# SysP_Uebersicht.net
KiCad netlist of a schematic drawn in Altium Designer
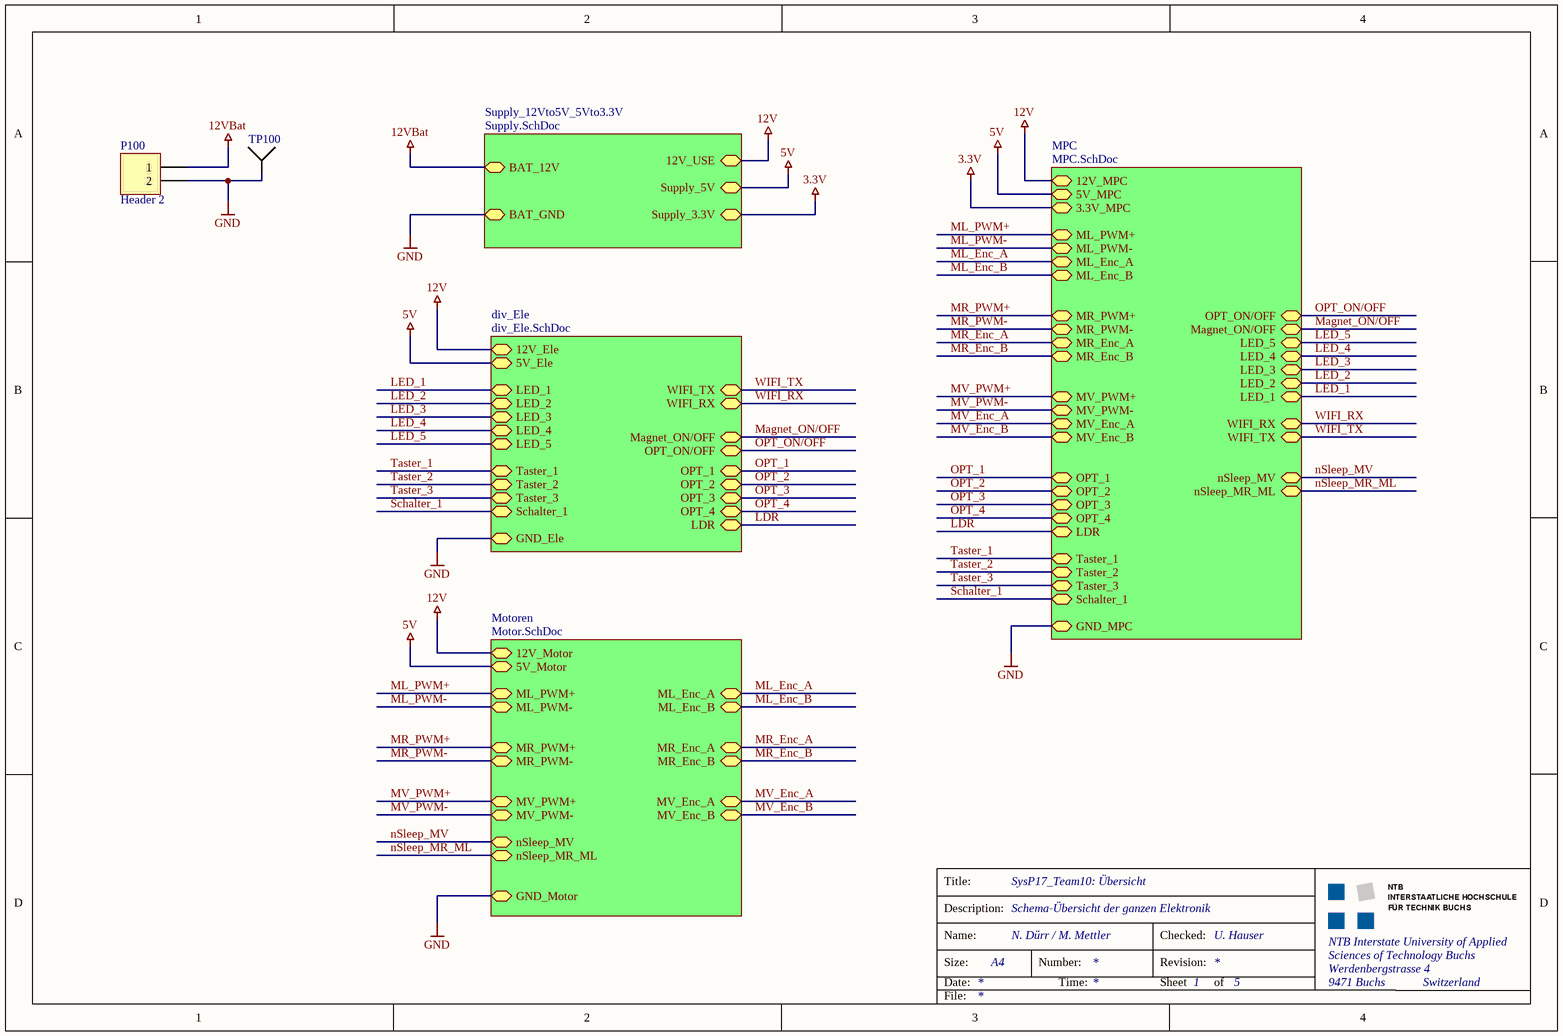
[diagram p0: SysP_Uebersicht.SchDoc]

(export (version "E")
  (design (tool "Eeschema 10.0.6"))
  (components
    (comp (ref "P100")
      (value "Header 2")
      (footprint "Connector_Bat_2")
      (description "Header, 2-Pin")
      (fields (field (name "PUBLISHER") "Altium Limited"))
      (libsource (lib "Miscellaneous Connectors") (part "Header 2"))
    )
    (comp (ref "TP100")
      (value "Testpunkt 1mm")
      (footprint "GEN_TP-THT-1.1mm_1_H")
      (fields (field (name "MANUFACTURER") "Keystone Electronics") (field (name "PUBLISHER") "B.Sc. Ursella"))
      (libsource (lib "IR-Sensor") (part "Testpunkt 1mm"))
    )
  )
  (nets
    (net (code "36") (name "12VBat") (class "Default")
      (node (ref "P100") (pin "1") (pinfunction "1_1") (pintype "passive"))
    )
    (net (code "37") (name "GND") (class "Default")
      (node (ref "P100") (pin "2") (pinfunction "2_2") (pintype "passive"))
      (node (ref "TP100") (pin "1") (pinfunction "0_1") (pintype "passive"))
    )
  )
)
